# adcbuffer.net
KiCad netlist of a schematic drawn in Altium Designer
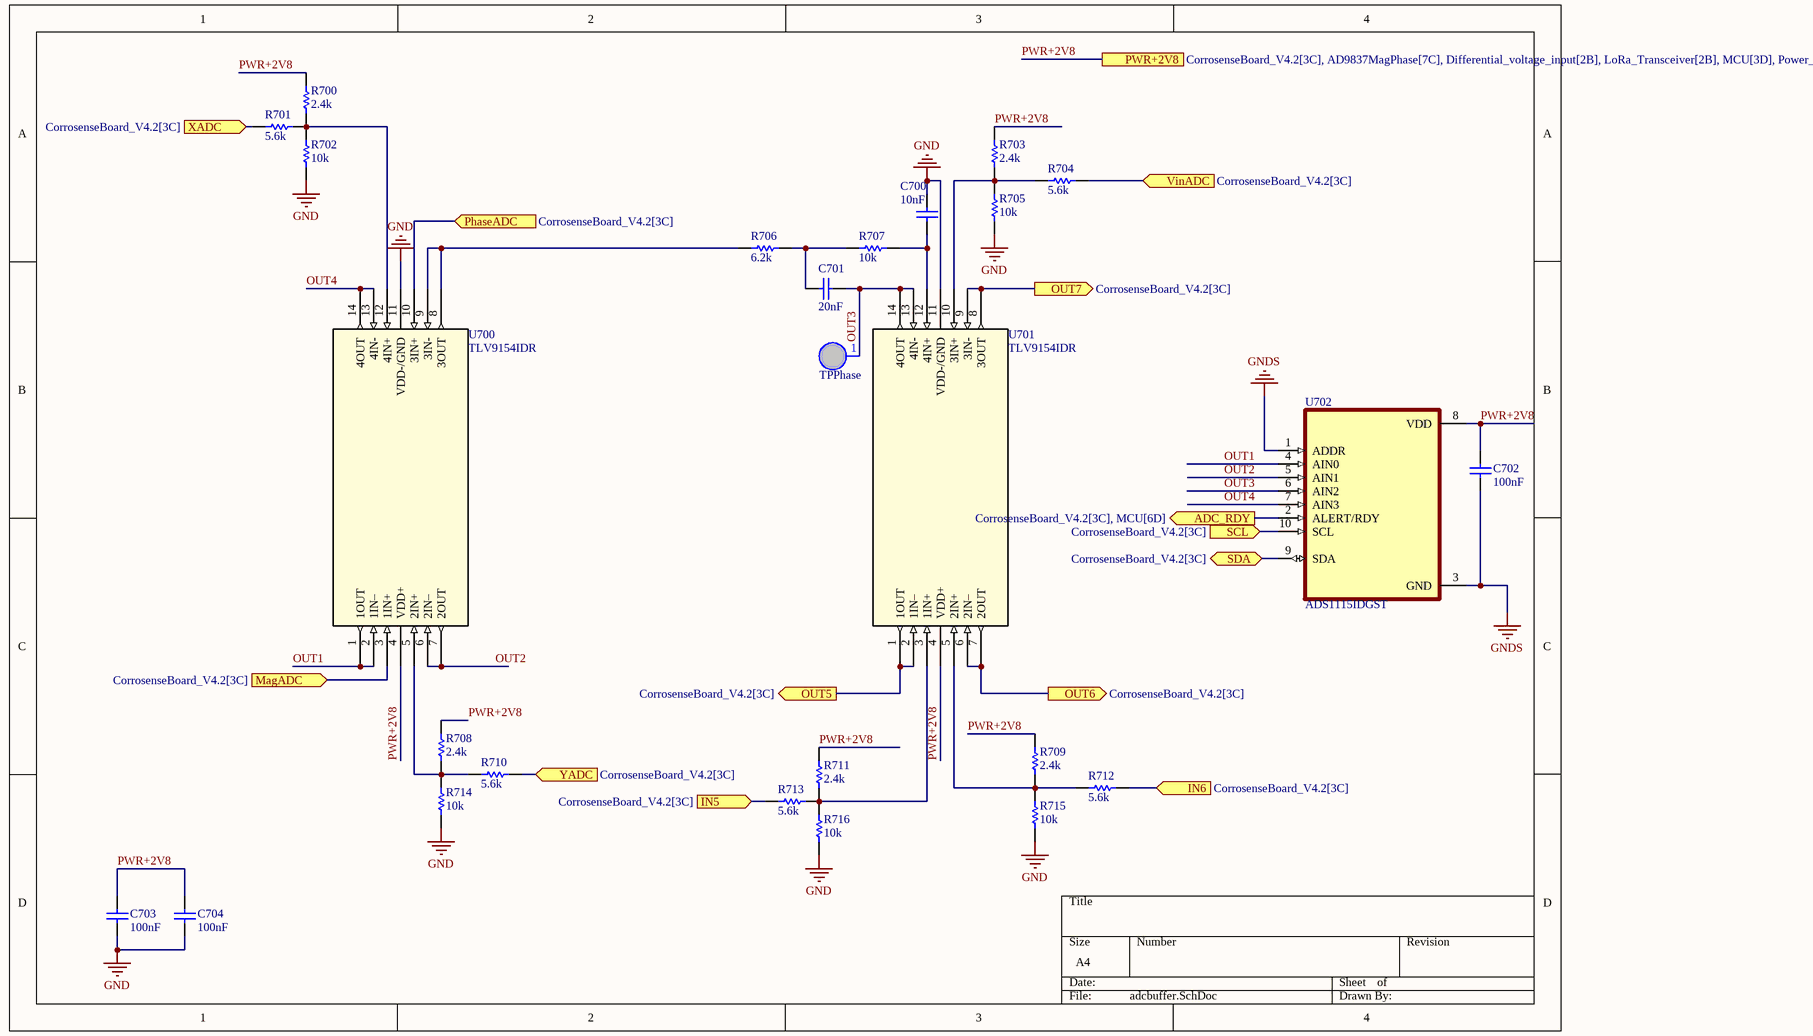
[diagram p0: adcbuffer.SchDoc]

(export (version "E")
  (design (tool "Eeschema 10.0.6"))
  (components
    (comp (ref "C700")
      (value "10nF")
      (footprint "1608[0603]")
      (description "CAP CER 25V X7R 0603")
      (fields (field (name "TOLERANCE") "±10%") (field (name "MANUFACTURER") "Murata Electronics"))
      (libsource (lib "Miscellaneous Devices") (part "Cap"))
    )
    (comp (ref "C701")
      (value "20nF")
      (footprint "1608[0603]")
      (description "CAP CER 25V X7R 0603")
      (fields (field (name "TOLERANCE") "±10%") (field (name "MANUFACTURER") "YAGEO"))
      (libsource (lib "Miscellaneous Devices") (part "Cap"))
    )
    (comp (ref "C702")
      (value "100nF")
      (footprint "1608[0603]")
      (description "CAP CER 25V X7R 0603")
      (fields (field (name "TOLERANCE") "±10%") (field (name "MANUFACTURER") "Murata Electronics"))
      (libsource (lib "Miscellaneous Devices") (part "Cap"))
    )
    (comp (ref "C703")
      (value "100nF")
      (footprint "1608[0603]")
      (description "CAP CER 25V X7R 0603")
      (fields (field (name "TOLERANCE") "±10%") (field (name "MANUFACTURER") "Murata Electronics"))
      (libsource (lib "Miscellaneous Devices") (part "Cap"))
    )
    (comp (ref "C704")
      (value "100nF")
      (footprint "1608[0603]")
      (description "CAP CER 25V X7R 0603")
      (fields (field (name "TOLERANCE") "±10%") (field (name "MANUFACTURER") "Murata Electronics"))
      (libsource (lib "Miscellaneous Devices") (part "Cap"))
    )
    (comp (ref "R700")
      (value "2.4k")
      (footprint "1608[0603]")
      (description "RES SMD 2% 1.5W 0603")
      (fields
        (field (name "MP") "-65°C ~ 155°C")
        (field (name "TOLERANCE") "2%")
        (field (name "PUBLISHER") "Altium Limited")
      )
      (libsource (lib "Res1") (part "Res1"))
    )
    (comp (ref "R701")
      (value "5.6k")
      (footprint "1608[0603]")
      (description "RES SMD 2% 1.5W 0603")
      (fields
        (field (name "MP") "-65°C ~ 155°C")
        (field (name "TOLERANCE") "2%")
        (field (name "PUBLISHER") "Altium Limited")
      )
      (libsource (lib "Res1") (part "Res1"))
    )
    (comp (ref "R702")
      (value "10k")
      (footprint "1608[0603]")
      (description "RES SMD 2% 1.5W 0603")
      (fields
        (field (name "MP") "-65°C ~ 155°C")
        (field (name "TOLERANCE") "2%")
        (field (name "PUBLISHER") "Altium Limited")
      )
      (libsource (lib "Res1") (part "Res1"))
    )
    (comp (ref "R703")
      (value "2.4k")
      (footprint "1608[0603]")
      (description "RES SMD 2% 1.5W 0603")
      (fields
        (field (name "MP") "-65°C ~ 155°C")
        (field (name "TOLERANCE") "2%")
        (field (name "PUBLISHER") "Altium Limited")
      )
      (libsource (lib "Res1") (part "Res1"))
    )
    (comp (ref "R704")
      (value "5.6k")
      (footprint "1608[0603]")
      (description "RES SMD 2% 1.5W 0603")
      (fields
        (field (name "MP") "-65°C ~ 155°C")
        (field (name "TOLERANCE") "2%")
        (field (name "PUBLISHER") "Altium Limited")
      )
      (libsource (lib "Res1") (part "Res1"))
    )
    (comp (ref "R705")
      (value "10k")
      (footprint "1608[0603]")
      (description "RES SMD 2% 1.5W 0603")
      (fields
        (field (name "MP") "-65°C ~ 155°C")
        (field (name "TOLERANCE") "2%")
        (field (name "PUBLISHER") "Altium Limited")
      )
      (libsource (lib "Res1") (part "Res1"))
    )
    (comp (ref "R706")
      (value "6.2k")
      (footprint "1608[0603]")
      (description "RES SMD 2% 1.5W 0603")
      (fields
        (field (name "MP") "-65°C ~ 155°C")
        (field (name "TOLERANCE") "2%")
        (field (name "PUBLISHER") "Altium Limited")
      )
      (libsource (lib "Res1") (part "Res1"))
    )
    (comp (ref "R707")
      (value "10k")
      (footprint "1608[0603]")
      (description "RES SMD 2% 1.5W 0603")
      (fields
        (field (name "MP") "-65°C ~ 155°C")
        (field (name "TOLERANCE") "2%")
        (field (name "PUBLISHER") "Altium Limited")
      )
      (libsource (lib "Res1") (part "Res1"))
    )
    (comp (ref "R708")
      (value "2.4k")
      (footprint "1608[0603]")
      (description "RES SMD 2% 1.5W 0603")
      (fields
        (field (name "MP") "-65°C ~ 155°C")
        (field (name "TOLERANCE") "2%")
        (field (name "PUBLISHER") "Altium Limited")
      )
      (libsource (lib "Res1") (part "Res1"))
    )
    (comp (ref "R709")
      (value "2.4k")
      (footprint "1608[0603]")
      (description "RES SMD 2% 1.5W 0603")
      (fields
        (field (name "MP") "-65°C ~ 155°C")
        (field (name "TOLERANCE") "2%")
        (field (name "PUBLISHER") "Altium Limited")
      )
      (libsource (lib "Res1") (part "Res1"))
    )
    (comp (ref "R710")
      (value "5.6k")
      (footprint "1608[0603]")
      (description "RES SMD 2% 1.5W 0603")
      (fields
        (field (name "MP") "-65°C ~ 155°C")
        (field (name "TOLERANCE") "2%")
        (field (name "PUBLISHER") "Altium Limited")
      )
      (libsource (lib "Res1") (part "Res1"))
    )
    (comp (ref "R711")
      (value "2.4k")
      (footprint "1608[0603]")
      (description "RES SMD 2% 1.5W 0603")
      (fields
        (field (name "MP") "-65°C ~ 155°C")
        (field (name "TOLERANCE") "2%")
        (field (name "PUBLISHER") "Altium Limited")
      )
      (libsource (lib "Res1") (part "Res1"))
    )
    (comp (ref "R712")
      (value "5.6k")
      (footprint "1608[0603]")
      (description "RES SMD 2% 1.5W 0603")
      (fields
        (field (name "MP") "-65°C ~ 155°C")
        (field (name "TOLERANCE") "2%")
        (field (name "PUBLISHER") "Altium Limited")
      )
      (libsource (lib "Res1") (part "Res1"))
    )
    (comp (ref "R713")
      (value "5.6k")
      (footprint "1608[0603]")
      (description "RES SMD 2% 1.5W 0603")
      (fields
        (field (name "MP") "-65°C ~ 155°C")
        (field (name "TOLERANCE") "2%")
        (field (name "PUBLISHER") "Altium Limited")
      )
      (libsource (lib "Res1") (part "Res1"))
    )
    (comp (ref "R714")
      (value "10k")
      (footprint "1608[0603]")
      (description "RES SMD 2% 1.5W 0603")
      (fields
        (field (name "MP") "-65°C ~ 155°C")
        (field (name "TOLERANCE") "2%")
        (field (name "PUBLISHER") "Altium Limited")
      )
      (libsource (lib "Res1") (part "Res1"))
    )
    (comp (ref "R715")
      (value "10k")
      (footprint "1608[0603]")
      (description "RES SMD 2% 1.5W 0603")
      (fields
        (field (name "MP") "-65°C ~ 155°C")
        (field (name "TOLERANCE") "2%")
        (field (name "PUBLISHER") "Altium Limited")
      )
      (libsource (lib "Res1") (part "Res1"))
    )
    (comp (ref "R716")
      (value "10k")
      (footprint "1608[0603]")
      (description "RES SMD 2% 1.5W 0603")
      (fields
        (field (name "MP") "-65°C ~ 155°C")
        (field (name "TOLERANCE") "2%")
        (field (name "PUBLISHER") "Altium Limited")
      )
      (libsource (lib "Res1") (part "Res1"))
    )
    (comp (ref "TPPhase") (value "TP") (footprint "PCBComponent_1") (libsource (lib "TP") (part "TP")))
    (comp (ref "U700")
      (value "TLV9154IDR")
      (footprint "SOIC127P600X175-14N")
      (description "No Description Available")
      (fields (field (name "MANUFACTURER") "Texas Instruments"))
      (libsource (lib "TLV2444CD") (part "TLV2444CD"))
    )
    (comp (ref "U701")
      (value "TLV9154IDR")
      (footprint "SOIC127P600X175-14N")
      (description "No Description Available")
      (fields (field (name "MANUFACTURER") "Texas Instruments"))
      (libsource (lib "TLV2444CD") (part "TLV2444CD"))
    )
    (comp (ref "U702")
      (value "ADS1115IDGST")
      (footprint "SOP50P490X110-10N")
      (fields (field (name "MANUFACTURER") "Texas Instruments"))
      (libsource (lib "ADS1115IDGST") (part "ADS1115IDGST"))
    )
  )
  (nets
    (net (code "1") (name "/ADC_RDY") (class "Default")
      (node (ref "U702") (pin "2") (pinfunction "ALERT/RDY_2") (pintype "input"))
    )
    (net (code "2") (name "/IN5") (class "Default")
      (node (ref "R713") (pin "2") (pinfunction "2_2") (pintype "passive"))
    )
    (net (code "3") (name "/IN6") (class "Default")
      (node (ref "R712") (pin "2") (pinfunction "2_2") (pintype "passive"))
    )
    (net (code "4") (name "/MagADC") (class "Default")
      (node (ref "U700") (pin "3") (pinfunction "1IN+_3") (pintype "input"))
    )
    (net (code "5") (name "/OUT1") (class "Default")
      (node (ref "U700") (pin "1") (pinfunction "1OUT_1") (pintype "output"))
      (node (ref "U700") (pin "2") (pinfunction "1IN–_2") (pintype "input"))
      (node (ref "U702") (pin "4") (pinfunction "AIN0_4") (pintype "input"))
    )
    (net (code "6") (name "/OUT2") (class "Default")
      (node (ref "U700") (pin "6") (pinfunction "2IN–_6") (pintype "input"))
      (node (ref "U700") (pin "7") (pinfunction "2OUT_7") (pintype "output"))
      (node (ref "U702") (pin "5") (pinfunction "AIN1_5") (pintype "input"))
    )
    (net (code "7") (name "/OUT3") (class "Default")
      (node (ref "C701") (pin "2") (pinfunction "2_2") (pintype "passive"))
      (node (ref "TPPhase") (pin "1") (pinfunction "6_1") (pintype "passive"))
      (node (ref "U701") (pin "13") (pinfunction "4IN-_13") (pintype "input"))
      (node (ref "U701") (pin "14") (pinfunction "4OUT_14") (pintype "output"))
      (node (ref "U702") (pin "6") (pinfunction "AIN2_6") (pintype "input"))
    )
    (net (code "8") (name "/OUT4") (class "Default")
      (node (ref "U700") (pin "13") (pinfunction "4IN-_13") (pintype "input"))
      (node (ref "U700") (pin "14") (pinfunction "4OUT_14") (pintype "output"))
      (node (ref "U702") (pin "7") (pinfunction "AIN3_7") (pintype "input"))
    )
    (net (code "9") (name "/OUT5") (class "Default")
      (node (ref "U701") (pin "1") (pinfunction "1OUT_1") (pintype "output"))
      (node (ref "U701") (pin "2") (pinfunction "1IN–_2") (pintype "input"))
    )
    (net (code "10") (name "/OUT6") (class "Default")
      (node (ref "U701") (pin "6") (pinfunction "2IN–_6") (pintype "input"))
      (node (ref "U701") (pin "7") (pinfunction "2OUT_7") (pintype "output"))
    )
    (net (code "11") (name "/OUT7") (class "Default")
      (node (ref "U701") (pin "8") (pinfunction "3OUT_8") (pintype "output"))
      (node (ref "U701") (pin "9") (pinfunction "3IN-_9") (pintype "input"))
    )
    (net (code "12") (name "/PWR+2V8") (class "Default")
      (node (ref "C702") (pin "1") (pinfunction "1_1") (pintype "passive"))
      (node (ref "C703") (pin "1") (pinfunction "1_1") (pintype "passive"))
      (node (ref "C704") (pin "1") (pinfunction "1_1") (pintype "passive"))
      (node (ref "R700") (pin "2") (pinfunction "2_2") (pintype "passive"))
      (node (ref "R703") (pin "2") (pinfunction "2_2") (pintype "passive"))
      (node (ref "R708") (pin "2") (pinfunction "2_2") (pintype "passive"))
      (node (ref "R709") (pin "2") (pinfunction "2_2") (pintype "passive"))
      (node (ref "R711") (pin "2") (pinfunction "2_2") (pintype "passive"))
      (node (ref "U700") (pin "4") (pinfunction "VDD+_4") (pintype "power_in"))
      (node (ref "U701") (pin "4") (pinfunction "VDD+_4") (pintype "power_in"))
      (node (ref "U702") (pin "8") (pinfunction "VDD_8") (pintype "power_in"))
    )
    (net (code "13") (name "/PhaseADC") (class "Default")
      (node (ref "U700") (pin "10") (pinfunction "3IN+_10") (pintype "input"))
    )
    (net (code "14") (name "/SCL") (class "Default")
      (node (ref "U702") (pin "10") (pinfunction "SCL_10") (pintype "input"))
    )
    (net (code "15") (name "/SDA") (class "Default")
      (node (ref "U702") (pin "9") (pinfunction "SDA_9") (pintype "bidirectional"))
    )
    (net (code "16") (name "/VinADC") (class "Default")
      (node (ref "R704") (pin "2") (pinfunction "2_2") (pintype "passive"))
    )
    (net (code "17") (name "/XADC") (class "Default")
      (node (ref "R701") (pin "2") (pinfunction "2_2") (pintype "passive"))
    )
    (net (code "18") (name "/YADC") (class "Default")
      (node (ref "R710") (pin "2") (pinfunction "2_2") (pintype "passive"))
    )
    (net (code "19") (name "GND") (class "Default")
      (node (ref "C700") (pin "2") (pinfunction "2_2") (pintype "passive"))
      (node (ref "C703") (pin "2") (pinfunction "2_2") (pintype "passive"))
      (node (ref "C704") (pin "2") (pinfunction "2_2") (pintype "passive"))
      (node (ref "R702") (pin "1") (pinfunction "1_1") (pintype "passive"))
      (node (ref "R705") (pin "1") (pinfunction "1_1") (pintype "passive"))
      (node (ref "R714") (pin "1") (pinfunction "1_1") (pintype "passive"))
      (node (ref "R715") (pin "1") (pinfunction "1_1") (pintype "passive"))
      (node (ref "R716") (pin "1") (pinfunction "1_1") (pintype "passive"))
      (node (ref "U700") (pin "11") (pinfunction "VDD-/GND_11") (pintype "power_in"))
      (node (ref "U701") (pin "11") (pinfunction "VDD-/GND_11") (pintype "power_in"))
    )
    (net (code "20") (name "GNDS") (class "Default")
      (node (ref "C702") (pin "2") (pinfunction "2_2") (pintype "passive"))
      (node (ref "U702") (pin "1") (pinfunction "ADDR_1") (pintype "input"))
      (node (ref "U702") (pin "3") (pinfunction "GND_3") (pintype "power_in"))
    )
    (net (code "21") (name "Net-(C701-Pad1)") (class "Default")
      (node (ref "C701") (pin "1") (pinfunction "1_1") (pintype "passive"))
      (node (ref "R706") (pin "1") (pinfunction "1_1") (pintype "passive"))
      (node (ref "R707") (pin "2") (pinfunction "2_2") (pintype "passive"))
    )
    (net (code "22") (name "Net-(U700-2IN+)") (class "Default")
      (node (ref "R708") (pin "1") (pinfunction "1_1") (pintype "passive"))
      (node (ref "R710") (pin "1") (pinfunction "1_1") (pintype "passive"))
      (node (ref "R714") (pin "2") (pinfunction "2_2") (pintype "passive"))
      (node (ref "U700") (pin "5") (pinfunction "2IN+_5") (pintype "input"))
    )
    (net (code "23") (name "Net-(U700-3IN-)") (class "Default")
      (node (ref "R706") (pin "2") (pinfunction "2_2") (pintype "passive"))
      (node (ref "U700") (pin "8") (pinfunction "3OUT_8") (pintype "output"))
      (node (ref "U700") (pin "9") (pinfunction "3IN-_9") (pintype "input"))
    )
    (net (code "24") (name "Net-(U700-4IN+)") (class "Default")
      (node (ref "R700") (pin "1") (pinfunction "1_1") (pintype "passive"))
      (node (ref "R701") (pin "1") (pinfunction "1_1") (pintype "passive"))
      (node (ref "R702") (pin "2") (pinfunction "2_2") (pintype "passive"))
      (node (ref "U700") (pin "12") (pinfunction "4IN+_12") (pintype "input"))
    )
    (net (code "25") (name "Net-(U701-1IN+)") (class "Default")
      (node (ref "R711") (pin "1") (pinfunction "1_1") (pintype "passive"))
      (node (ref "R713") (pin "1") (pinfunction "1_1") (pintype "passive"))
      (node (ref "R716") (pin "2") (pinfunction "2_2") (pintype "passive"))
      (node (ref "U701") (pin "3") (pinfunction "1IN+_3") (pintype "input"))
    )
    (net (code "26") (name "Net-(U701-2IN+)") (class "Default")
      (node (ref "R709") (pin "1") (pinfunction "1_1") (pintype "passive"))
      (node (ref "R712") (pin "1") (pinfunction "1_1") (pintype "passive"))
      (node (ref "R715") (pin "2") (pinfunction "2_2") (pintype "passive"))
      (node (ref "U701") (pin "5") (pinfunction "2IN+_5") (pintype "input"))
    )
    (net (code "27") (name "Net-(U701-3IN+)") (class "Default")
      (node (ref "R703") (pin "1") (pinfunction "1_1") (pintype "passive"))
      (node (ref "R704") (pin "1") (pinfunction "1_1") (pintype "passive"))
      (node (ref "R705") (pin "2") (pinfunction "2_2") (pintype "passive"))
      (node (ref "U701") (pin "10") (pinfunction "3IN+_10") (pintype "input"))
    )
    (net (code "28") (name "Net-(U701-4IN+)") (class "Default")
      (node (ref "C700") (pin "1") (pinfunction "1_1") (pintype "passive"))
      (node (ref "R707") (pin "1") (pinfunction "1_1") (pintype "passive"))
      (node (ref "U701") (pin "12") (pinfunction "4IN+_12") (pintype "input"))
    )
  )
)
